# TIDA-00830_DRV888x.net
KiCad netlist of a schematic drawn in Altium Designer
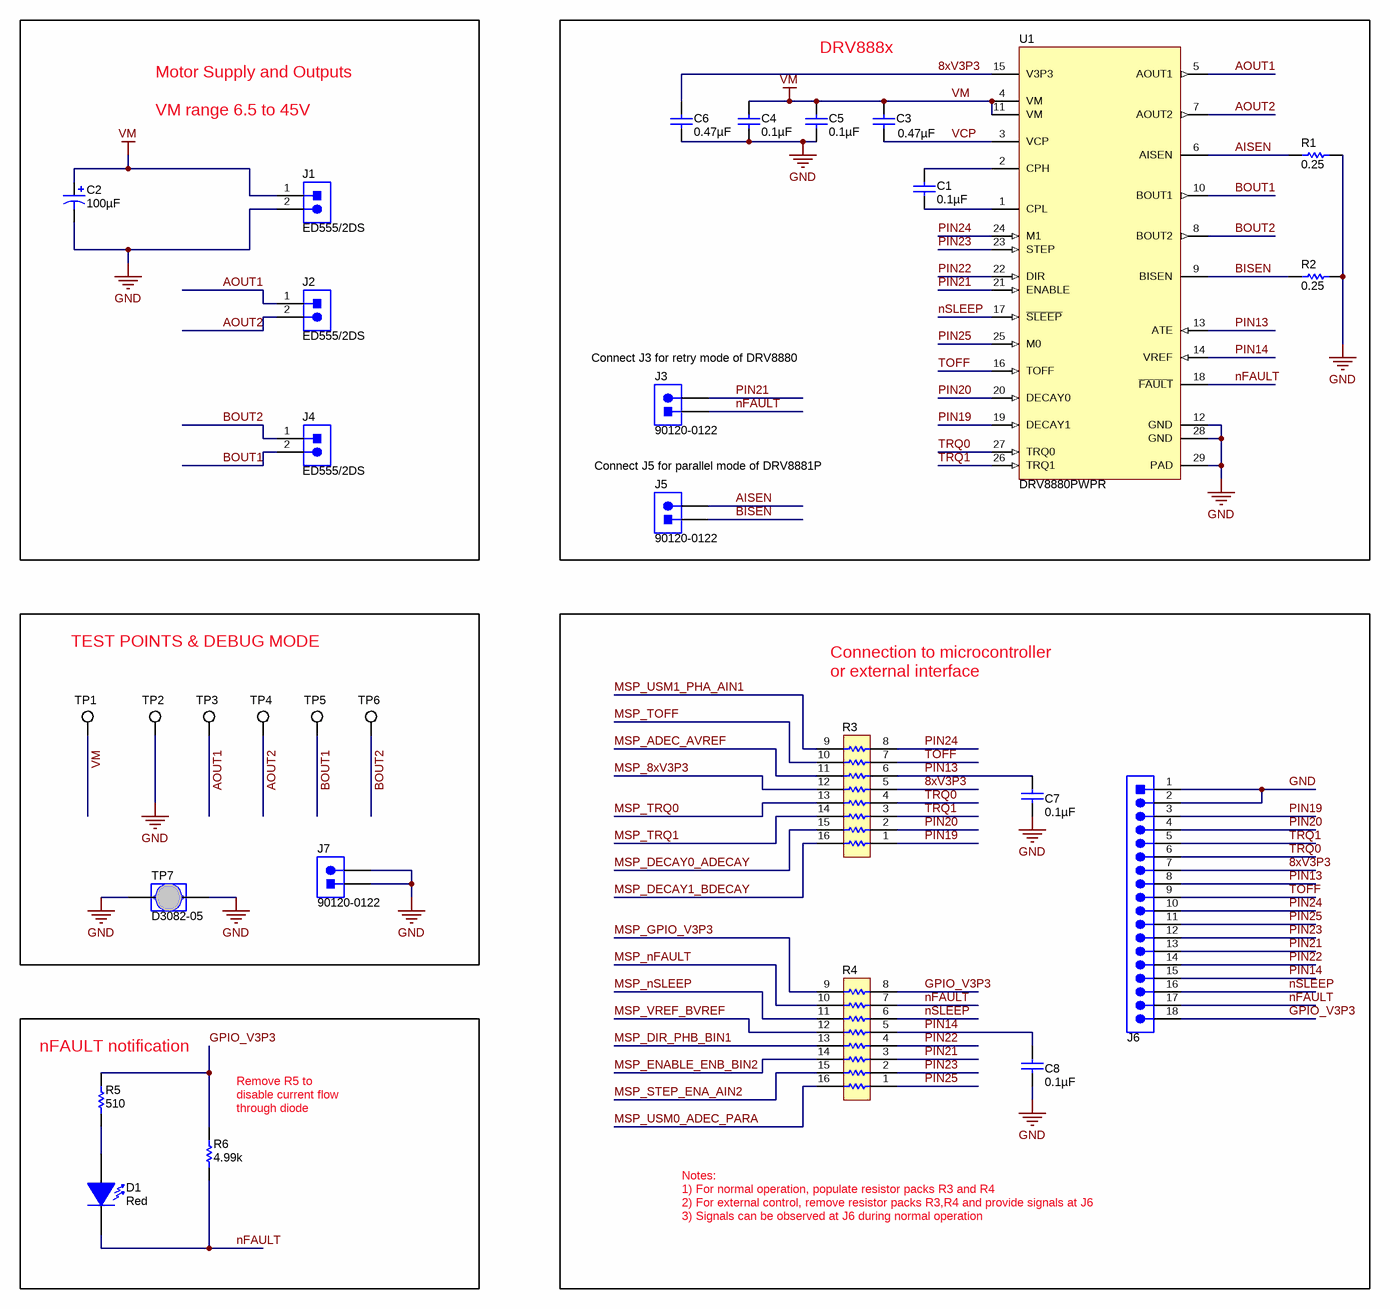
[diagram p0: TIDA-00830_DRV888x.SchDoc]

(export (version "E")
  (design (tool "Eeschema 10.0.6"))
  (components
    (comp (ref "C1")
      (value "C0805C104K1RACTU")
      (footprint "0805L")
      (description "CAP, CERM, 0.1 µF, 100 V, +/- 10%, X7R, 0805")
      (fields
        (field (name "VALUEDISPLAYED") "0.1µF")
        (field (name "MANUFACTURER") "Kemet")
        (field (name "PUBLISHER") "Texas Instruments")
      )
      (libsource (lib "Capacitor_Ceramic") (part "C0805C104K1RACTU"))
    )
    (comp (ref "C2")
      (value "EEE-FK1J101P")
      (footprint "SM_RADIAL_G")
      (description "CAP, AL, 100 µF, 63 V, +/- 20%, 0.35 ohm, SMD")
      (fields
        (field (name "MANUFACTURER") "Panasonic")
        (field (name "VALUEDISPLAYED") "100µF")
        (field (name "PUBLISHER") "Texas Instruments")
      )
      (libsource (lib "Capacitor_Aluminum") (part "EEE-FK1J101P"))
    )
    (comp (ref "C3")
      (value "C2012X7R1E474K")
      (footprint "0805L")
      (description "CAP, CERM, 0.47 µF, 25 V, +/- 10%, X7R, 0805")
      (fields
        (field (name "VALUEDISPLAYED") "0.47µF")
        (field (name "MANUFACTURER") "TDK")
        (field (name "PUBLISHER") "Texas Instruments")
      )
      (libsource (lib "Capacitor_Ceramic") (part "C2012X7R1E474K"))
    )
    (comp (ref "C4")
      (value "C0805C104K1RACTU")
      (footprint "0805L")
      (description "CAP, CERM, 0.1 µF, 100 V, +/- 10%, X7R, 0805")
      (fields
        (field (name "VALUEDISPLAYED") "0.1µF")
        (field (name "MANUFACTURER") "Kemet")
        (field (name "PUBLISHER") "Texas Instruments")
      )
      (libsource (lib "Capacitor_Ceramic") (part "C0805C104K1RACTU"))
    )
    (comp (ref "C5")
      (value "C0805C104K1RACTU")
      (footprint "0805L")
      (description "CAP, CERM, 0.1 µF, 100 V, +/- 10%, X7R, 0805")
      (fields
        (field (name "VALUEDISPLAYED") "0.1µF")
        (field (name "MANUFACTURER") "Kemet")
        (field (name "PUBLISHER") "Texas Instruments")
      )
      (libsource (lib "Capacitor_Ceramic") (part "C0805C104K1RACTU"))
    )
    (comp (ref "C6")
      (value "C0603C474K9RACTU")
      (footprint "0603L")
      (description "CAP, CERM, 0.47 µF, 6.3 V, +/- 10%, X7R, 0603")
      (fields
        (field (name "VALUEDISPLAYED") "0.47µF")
        (field (name "MANUFACTURER") "Kemet")
        (field (name "PUBLISHER") "Texas Instruments")
      )
      (libsource (lib "Capacitor_Ceramic") (part "C0603C474K9RACTU"))
    )
    (comp (ref "C7")
      (value "GRM155R61A104KA01D")
      (footprint "0402L")
      (description "CAP, CERM, 0.1 µF, 10 V, +/- 10%, X5R, 0402")
      (fields
        (field (name "MANUFACTURER") "MuRata")
        (field (name "VALUEDISPLAYED") "0.1µF")
        (field (name "PUBLISHER") "Texas Instruments")
      )
      (libsource (lib "Capacitor_Ceramic") (part "GRM155R61A104KA01D"))
    )
    (comp (ref "C8")
      (value "GRM155R61A104KA01D")
      (footprint "0402L")
      (description "CAP, CERM, 0.1 µF, 10 V, +/- 10%, X5R, 0402")
      (fields
        (field (name "MANUFACTURER") "MuRata")
        (field (name "VALUEDISPLAYED") "0.1µF")
        (field (name "PUBLISHER") "Texas Instruments")
      )
      (libsource (lib "Capacitor_Ceramic") (part "GRM155R61A104KA01D"))
    )
    (comp (ref "D1")
      (value "Red")
      (footprint "LED_LTST-C190_Red")
      (description "LED, Red, SMD")
      (fields
        (field (name "PARTNUMBER") "LTST-C190CKT")
        (field (name "MANUFACTURER") "Lite-On")
        (field (name "PUBLISHER") "Texas Instruments")
      )
      (libsource (lib "LED") (part "LTST-C190CKT"))
    )
    (comp (ref "J1")
      (value "ED555/2DS")
      (footprint "TERM_BLK_ED555-2DS")
      (description "Terminal Block, 6A, 3.5mm Pitch, 2-Pos, TH")
      (fields
        (field (name "MANUFACTURER") "On-Shore Technology")
        (field (name "SYMBOLCREATOR") "a0412235")
        (field (name "PUBLISHER") "Texas Instruments")
      )
      (libsource (lib "Connectors_Other") (part "ED555/2DS"))
    )
    (comp (ref "J2")
      (value "ED555/2DS")
      (footprint "TERM_BLK_ED555-2DS")
      (description "Terminal Block, 6A, 3.5mm Pitch, 2-Pos, TH")
      (fields
        (field (name "MANUFACTURER") "On-Shore Technology")
        (field (name "SYMBOLCREATOR") "a0412235")
        (field (name "PUBLISHER") "Texas Instruments")
      )
      (libsource (lib "Connectors_Other") (part "ED555/2DS"))
    )
    (comp (ref "J3")
      (value "90120-0122")
      (footprint "CONN_90120-0122")
      (description "Header, 100mil, 2x1, Tin, TH")
      (fields
        (field (name "MANUFACTURER") "Molex")
        (field (name "SYMBOLCREATOR") "a0412235")
        (field (name "PUBLISHER") "Texas Instruments")
      )
      (libsource (lib "Connectors_Molex") (part "90120-0122"))
    )
    (comp (ref "J4")
      (value "ED555/2DS")
      (footprint "TERM_BLK_ED555-2DS")
      (description "Terminal Block, 6A, 3.5mm Pitch, 2-Pos, TH")
      (fields
        (field (name "MANUFACTURER") "On-Shore Technology")
        (field (name "SYMBOLCREATOR") "a0412235")
        (field (name "PUBLISHER") "Texas Instruments")
      )
      (libsource (lib "Connectors_Other") (part "ED555/2DS"))
    )
    (comp (ref "J5")
      (value "90120-0122")
      (footprint "CONN_90120-0122")
      (description "Header, 100mil, 2x1, Tin, TH")
      (fields
        (field (name "MANUFACTURER") "Molex")
        (field (name "SYMBOLCREATOR") "a0412235")
        (field (name "PUBLISHER") "Texas Instruments")
      )
      (libsource (lib "Connectors_Molex") (part "90120-0122"))
    )
    (comp (ref "J6")
      (value "TSW-118-07-G-S")
      (footprint "TSW-118-07-G-S")
      (description "Header, 100mil, 18x1, Gold, TH")
      (fields
        (field (name "MANUFACTURER") "Samtec")
        (field (name "SYMBOLCREATOR") "a0411947")
        (field (name "PUBLISHER") "Texas Instruments")
      )
      (libsource (lib "Connectors_Samtec") (part "TSW-118-07-G-S"))
    )
    (comp (ref "J7")
      (value "90120-0122")
      (footprint "CONN_90120-0122")
      (description "Header, 100mil, 2x1, Tin, TH")
      (fields
        (field (name "MANUFACTURER") "Molex")
        (field (name "SYMBOLCREATOR") "a0412235")
        (field (name "PUBLISHER") "Texas Instruments")
      )
      (libsource (lib "Connectors_Molex") (part "90120-0122"))
    )
    (comp (ref "R1")
      (value "0.25")
      (footprint "2010L")
      (description "RES, 0.25, 1%, 1 W, 2010")
      (fields
        (field (name "PARTNUMBER") "CSRN2010FKR250")
        (field (name "MANUFACTURER") "Stackpole Electronics Inc")
        (field (name "PUBLISHER") "Texas Instruments")
      )
      (libsource (lib "Resistor_2010") (part "CSRN2010FKR250"))
    )
    (comp (ref "R2")
      (value "0.25")
      (footprint "2010L")
      (description "RES, 0.25, 1%, 1 W, 2010")
      (fields
        (field (name "PARTNUMBER") "CSRN2010FKR250")
        (field (name "MANUFACTURER") "Stackpole Electronics Inc")
        (field (name "PUBLISHER") "Texas Instruments")
      )
      (libsource (lib "Resistor_2010") (part "CSRN2010FKR250"))
    )
    (comp (ref "R3")
      (value "EXB-2HV330JV")
      (footprint "RESCAXS_EXB-2HV")
      (description "RES, 33, 5%, 0.0625 W, Resistor Array - 8x1")
      (fields
        (field (name "MANUFACTURER") "Panasonic")
        (field (name "SYMBOLCREATOR") "a0411947")
        (field (name "PUBLISHER") "Texas Instruments")
      )
      (libsource (lib "Resistor_OtherSMT") (part "EXB-2HV330JV"))
    )
    (comp (ref "R4")
      (value "EXB-2HV330JV")
      (footprint "RESCAXS_EXB-2HV")
      (description "RES, 33, 5%, 0.0625 W, Resistor Array - 8x1")
      (fields
        (field (name "MANUFACTURER") "Panasonic")
        (field (name "SYMBOLCREATOR") "a0411947")
        (field (name "PUBLISHER") "Texas Instruments")
      )
      (libsource (lib "Resistor_OtherSMT") (part "EXB-2HV330JV"))
    )
    (comp (ref "R5")
      (value "510")
      (footprint "0402L")
      (description "RES, 510, 5%, 0.063 W, 0402")
      (fields
        (field (name "PARTNUMBER") "CRCW0402510RJNED")
        (field (name "MANUFACTURER") "Vishay-Dale")
        (field (name "PUBLISHER") "Texas Instruments")
      )
      (libsource (lib "Resistor_0402") (part "CRCW0402510RJNED"))
    )
    (comp (ref "R6")
      (value "4.99k")
      (footprint "0402L")
      (description "RES, 4.99 k, 1%, 0.063 W, 0402")
      (fields
        (field (name "PARTNUMBER") "CRCW04024K99FKED")
        (field (name "MANUFACTURER") "Vishay-Dale")
        (field (name "PUBLISHER") "Texas Instruments")
      )
      (libsource (lib "Resistor_0402") (part "CRCW04024K99FKED"))
    )
    (comp (ref "TP1")
      (value "5016")
      (footprint "Testpoint_Keystone_Compact")
      (description "Test Point, Compact, SMT")
      (fields (field (name "MANUFACTURER") "Keystone") (field (name "PUBLISHER") "Texas Instruments"))
      (libsource (lib "Connectors_Keystone") (part "5016"))
    )
    (comp (ref "TP2")
      (value "5016")
      (footprint "Testpoint_Keystone_Compact")
      (description "Test Point, Compact, SMT")
      (fields (field (name "MANUFACTURER") "Keystone") (field (name "PUBLISHER") "Texas Instruments"))
      (libsource (lib "Connectors_Keystone") (part "5016"))
    )
    (comp (ref "TP3")
      (value "5016")
      (footprint "Testpoint_Keystone_Compact")
      (description "Test Point, Compact, SMT")
      (fields (field (name "MANUFACTURER") "Keystone") (field (name "PUBLISHER") "Texas Instruments"))
      (libsource (lib "Connectors_Keystone") (part "5016"))
    )
    (comp (ref "TP4")
      (value "5016")
      (footprint "Testpoint_Keystone_Compact")
      (description "Test Point, Compact, SMT")
      (fields (field (name "MANUFACTURER") "Keystone") (field (name "PUBLISHER") "Texas Instruments"))
      (libsource (lib "Connectors_Keystone") (part "5016"))
    )
    (comp (ref "TP5")
      (value "5016")
      (footprint "Testpoint_Keystone_Compact")
      (description "Test Point, Compact, SMT")
      (fields (field (name "MANUFACTURER") "Keystone") (field (name "PUBLISHER") "Texas Instruments"))
      (libsource (lib "Connectors_Keystone") (part "5016"))
    )
    (comp (ref "TP6")
      (value "5016")
      (footprint "Testpoint_Keystone_Compact")
      (description "Test Point, Compact, SMT")
      (fields (field (name "MANUFACTURER") "Keystone") (field (name "PUBLISHER") "Texas Instruments"))
      (libsource (lib "Connectors_Keystone") (part "5016"))
    )
    (comp (ref "TP7")
      (value "D3082-05")
      (footprint "Harwin_D3082-05")
      (description "1mm Uninsulated Shorting Plug, 10.16mm spacing, TH")
      (fields
        (field (name "MANUFACTURER") "Harwin")
        (field (name "SYMBOLCREATOR") "a0799628")
        (field (name "PUBLISHER") "Texas Instruments")
      )
      (libsource (lib "Connectors_Other") (part "D3082-05"))
    )
    (comp (ref "U1")
      (value "DRV8880PWPR")
      (footprint "PWP0028C_N")
      (description "2-A 45-V 1/16-μstep Stepper Motor Driver With AutoTune, PWP0028C")
      (fields
        (field (name "ALTERNATE PARTNUMBER") "DRV8880PWP")
        (field (name "MANUFACTURER") "Texas Instruments")
        (field (name "SYMBOLCREATOR") "Altium")
        (field (name "PUBLISHER") "Texas Instruments")
      )
      (libsource (lib "TI_Pre_RTM") (part "DRV8880PWPR"))
    )
  )
  (nets
    (net (code "1") (name "/8xV3P3") (class "Default")
      (node (ref "C6") (pin "1") (pinfunction "1_1") (pintype "passive"))
      (node (ref "J6") (pin "7") (pinfunction "7_7") (pintype "passive"))
      (node (ref "R3") (pin "5") (pinfunction "5_5") (pintype "passive"))
      (node (ref "U1") (pin "15") (pinfunction "V3P3_15") (pintype "power_in"))
    )
    (net (code "2") (name "/AISEN") (class "Default")
      (node (ref "J5") (pin "2") (pinfunction "2_2") (pintype "passive"))
      (node (ref "R1") (pin "2") (pinfunction "2_2") (pintype "passive"))
      (node (ref "U1") (pin "6") (pinfunction "AISEN_6") (pintype "passive"))
    )
    (net (code "3") (name "/AOUT1") (class "Default")
      (node (ref "J2") (pin "1") (pinfunction "1_1") (pintype "passive"))
      (node (ref "TP3") (pin "1") (pintype "passive"))
      (node (ref "U1") (pin "5") (pinfunction "AOUT1_5") (pintype "output"))
    )
    (net (code "4") (name "/AOUT2") (class "Default")
      (node (ref "J2") (pin "2") (pinfunction "2_2") (pintype "passive"))
      (node (ref "TP4") (pin "1") (pintype "passive"))
      (node (ref "U1") (pin "7") (pinfunction "AOUT2_7") (pintype "output"))
    )
    (net (code "5") (name "/BISEN") (class "Default")
      (node (ref "J5") (pin "1") (pinfunction "1_1") (pintype "passive"))
      (node (ref "R2") (pin "2") (pinfunction "2_2") (pintype "passive"))
      (node (ref "U1") (pin "9") (pinfunction "BISEN_9") (pintype "passive"))
    )
    (net (code "6") (name "/BOUT1") (class "Default")
      (node (ref "J4") (pin "2") (pinfunction "2_2") (pintype "passive"))
      (node (ref "TP5") (pin "1") (pintype "passive"))
      (node (ref "U1") (pin "10") (pinfunction "BOUT1_10") (pintype "output"))
    )
    (net (code "7") (name "/BOUT2") (class "Default")
      (node (ref "J4") (pin "1") (pinfunction "1_1") (pintype "passive"))
      (node (ref "TP6") (pin "1") (pintype "passive"))
      (node (ref "U1") (pin "8") (pinfunction "BOUT2_8") (pintype "output"))
    )
    (net (code "8") (name "/GPIO_V3P3") (class "Default")
      (node (ref "J6") (pin "18") (pinfunction "18_18") (pintype "passive"))
      (node (ref "R4") (pin "8") (pinfunction "8_8") (pintype "passive"))
      (node (ref "R5") (pin "2") (pinfunction "2_2") (pintype "passive"))
      (node (ref "R6") (pin "2") (pinfunction "2_2") (pintype "passive"))
    )
    (net (code "9") (name "/MSP_8xV3P3") (class "Default")
      (node (ref "R3") (pin "12") (pinfunction "12_12") (pintype "passive"))
    )
    (net (code "10") (name "/MSP_ADEC_AVREF") (class "Default")
      (node (ref "R3") (pin "11") (pinfunction "11_11") (pintype "passive"))
    )
    (net (code "11") (name "/MSP_DECAY0_ADECAY") (class "Default")
      (node (ref "R3") (pin "15") (pinfunction "15_15") (pintype "passive"))
    )
    (net (code "12") (name "/MSP_DECAY1_BDECAY") (class "Default")
      (node (ref "R3") (pin "16") (pinfunction "16_16") (pintype "passive"))
    )
    (net (code "13") (name "/MSP_DIR_PHB_BIN1") (class "Default")
      (node (ref "R4") (pin "13") (pinfunction "13_13") (pintype "passive"))
    )
    (net (code "14") (name "/MSP_ENABLE_ENB_BIN2") (class "Default")
      (node (ref "R4") (pin "14") (pinfunction "14_14") (pintype "passive"))
    )
    (net (code "15") (name "/MSP_GPIO_V3P3") (class "Default")
      (node (ref "R4") (pin "9") (pinfunction "9_9") (pintype "passive"))
    )
    (net (code "16") (name "/MSP_STEP_ENA_AIN2") (class "Default")
      (node (ref "R4") (pin "15") (pinfunction "15_15") (pintype "passive"))
    )
    (net (code "17") (name "/MSP_TOFF") (class "Default")
      (node (ref "R3") (pin "10") (pinfunction "10_10") (pintype "passive"))
    )
    (net (code "18") (name "/MSP_TRQ0") (class "Default")
      (node (ref "R3") (pin "13") (pinfunction "13_13") (pintype "passive"))
    )
    (net (code "19") (name "/MSP_TRQ1") (class "Default")
      (node (ref "R3") (pin "14") (pinfunction "14_14") (pintype "passive"))
    )
    (net (code "20") (name "/MSP_USM0_ADEC_PARA") (class "Default")
      (node (ref "R4") (pin "16") (pinfunction "16_16") (pintype "passive"))
    )
    (net (code "21") (name "/MSP_USM1_PHA_AIN1") (class "Default")
      (node (ref "R3") (pin "9") (pinfunction "9_9") (pintype "passive"))
    )
    (net (code "22") (name "/MSP_VREF_BVREF") (class "Default")
      (node (ref "R4") (pin "12") (pinfunction "12_12") (pintype "passive"))
    )
    (net (code "23") (name "/MSP_nFAULT") (class "Default")
      (node (ref "R4") (pin "10") (pinfunction "10_10") (pintype "passive"))
    )
    (net (code "24") (name "/MSP_nSLEEP") (class "Default")
      (node (ref "R4") (pin "11") (pinfunction "11_11") (pintype "passive"))
    )
    (net (code "25") (name "/PIN13") (class "Default")
      (node (ref "C7") (pin "1") (pinfunction "1_1") (pintype "passive"))
      (node (ref "J6") (pin "8") (pinfunction "8_8") (pintype "passive"))
      (node (ref "R3") (pin "6") (pinfunction "6_6") (pintype "passive"))
      (node (ref "U1") (pin "13") (pinfunction "ATE_13") (pintype "input"))
    )
    (net (code "26") (name "/PIN14") (class "Default")
      (node (ref "C8") (pin "1") (pinfunction "1_1") (pintype "passive"))
      (node (ref "J6") (pin "15") (pinfunction "15_15") (pintype "passive"))
      (node (ref "R4") (pin "5") (pinfunction "5_5") (pintype "passive"))
      (node (ref "U1") (pin "14") (pinfunction "VREF_14") (pintype "input"))
    )
    (net (code "27") (name "/PIN19") (class "Default")
      (node (ref "J6") (pin "3") (pinfunction "3_3") (pintype "passive"))
      (node (ref "R3") (pin "1") (pinfunction "1_1") (pintype "passive"))
      (node (ref "U1") (pin "19") (pinfunction "DECAY1_19") (pintype "input"))
    )
    (net (code "28") (name "/PIN20") (class "Default")
      (node (ref "J6") (pin "4") (pinfunction "4_4") (pintype "passive"))
      (node (ref "R3") (pin "2") (pinfunction "2_2") (pintype "passive"))
      (node (ref "U1") (pin "20") (pinfunction "DECAY0_20") (pintype "input"))
    )
    (net (code "29") (name "/PIN21") (class "Default")
      (node (ref "J3") (pin "2") (pinfunction "2_2") (pintype "passive"))
      (node (ref "J6") (pin "13") (pinfunction "13_13") (pintype "passive"))
      (node (ref "R4") (pin "3") (pinfunction "3_3") (pintype "passive"))
      (node (ref "U1") (pin "21") (pinfunction "ENABLE_21") (pintype "input"))
    )
    (net (code "30") (name "/PIN22") (class "Default")
      (node (ref "J6") (pin "14") (pinfunction "14_14") (pintype "passive"))
      (node (ref "R4") (pin "4") (pinfunction "4_4") (pintype "passive"))
      (node (ref "U1") (pin "22") (pinfunction "DIR_22") (pintype "input"))
    )
    (net (code "31") (name "/PIN23") (class "Default")
      (node (ref "J6") (pin "12") (pinfunction "12_12") (pintype "passive"))
      (node (ref "R4") (pin "2") (pinfunction "2_2") (pintype "passive"))
      (node (ref "U1") (pin "23") (pinfunction "STEP_23") (pintype "input"))
    )
    (net (code "32") (name "/PIN24") (class "Default")
      (node (ref "J6") (pin "10") (pinfunction "10_10") (pintype "passive"))
      (node (ref "R3") (pin "8") (pinfunction "8_8") (pintype "passive"))
      (node (ref "U1") (pin "24") (pinfunction "M1_24") (pintype "input"))
    )
    (net (code "33") (name "/PIN25") (class "Default")
      (node (ref "J6") (pin "11") (pinfunction "11_11") (pintype "passive"))
      (node (ref "R4") (pin "1") (pinfunction "1_1") (pintype "passive"))
      (node (ref "U1") (pin "25") (pinfunction "M0_25") (pintype "input"))
    )
    (net (code "34") (name "/TOFF") (class "Default")
      (node (ref "J6") (pin "9") (pinfunction "9_9") (pintype "passive"))
      (node (ref "R3") (pin "7") (pinfunction "7_7") (pintype "passive"))
      (node (ref "U1") (pin "16") (pinfunction "TOFF_16") (pintype "input"))
    )
    (net (code "35") (name "/TRQ0") (class "Default")
      (node (ref "J6") (pin "6") (pinfunction "6_6") (pintype "passive"))
      (node (ref "R3") (pin "4") (pinfunction "4_4") (pintype "passive"))
      (node (ref "U1") (pin "27") (pinfunction "TRQ0_27") (pintype "input"))
    )
    (net (code "36") (name "/TRQ1") (class "Default")
      (node (ref "J6") (pin "5") (pinfunction "5_5") (pintype "passive"))
      (node (ref "R3") (pin "3") (pinfunction "3_3") (pintype "passive"))
      (node (ref "U1") (pin "26") (pinfunction "TRQ1_26") (pintype "input"))
    )
    (net (code "37") (name "/VCP") (class "Default")
      (node (ref "C3") (pin "1") (pinfunction "1_1") (pintype "passive"))
      (node (ref "U1") (pin "3") (pinfunction "VCP_3") (pintype "passive"))
    )
    (net (code "38") (name "/nFAULT") (class "Default")
      (node (ref "D1") (pin "2") (pinfunction "K_2") (pintype "passive"))
      (node (ref "J3") (pin "1") (pinfunction "1_1") (pintype "passive"))
      (node (ref "J6") (pin "17") (pinfunction "17_17") (pintype "passive"))
      (node (ref "R4") (pin "7") (pinfunction "7_7") (pintype "passive"))
      (node (ref "R6") (pin "1") (pinfunction "1_1") (pintype "passive"))
      (node (ref "U1") (pin "18") (pinfunction "FAULT_18") (pintype "open_collector"))
    )
    (net (code "39") (name "/nSLEEP") (class "Default")
      (node (ref "J6") (pin "16") (pinfunction "16_16") (pintype "passive"))
      (node (ref "R4") (pin "6") (pinfunction "6_6") (pintype "passive"))
      (node (ref "U1") (pin "17") (pinfunction "SLEEP_17") (pintype "input"))
    )
    (net (code "40") (name "GND") (class "Default")
      (node (ref "C2") (pin "2") (pinfunction "-_2") (pintype "passive"))
      (node (ref "C4") (pin "1") (pinfunction "1_1") (pintype "passive"))
      (node (ref "C5") (pin "1") (pinfunction "1_1") (pintype "passive"))
      (node (ref "C6") (pin "2") (pinfunction "2_2") (pintype "passive"))
      (node (ref "C7") (pin "2") (pinfunction "2_2") (pintype "passive"))
      (node (ref "C8") (pin "2") (pinfunction "2_2") (pintype "passive"))
      (node (ref "J1") (pin "2") (pinfunction "2_2") (pintype "passive"))
      (node (ref "J6") (pin "1") (pinfunction "1_1") (pintype "passive"))
      (node (ref "J6") (pin "2") (pinfunction "2_2") (pintype "passive"))
      (node (ref "J7") (pin "1") (pinfunction "1_1") (pintype "passive"))
      (node (ref "J7") (pin "2") (pinfunction "2_2") (pintype "passive"))
      (node (ref "R1") (pin "1") (pinfunction "1_1") (pintype "passive"))
      (node (ref "R2") (pin "1") (pinfunction "1_1") (pintype "passive"))
      (node (ref "TP2") (pin "1") (pintype "passive"))
      (node (ref "TP7") (pin "1") (pinfunction "1_1") (pintype "passive"))
      (node (ref "TP7") (pin "2") (pinfunction "2_2") (pintype "passive"))
      (node (ref "U1") (pin "12") (pinfunction "GND_12") (pintype "power_in"))
      (node (ref "U1") (pin "28") (pinfunction "GND_28") (pintype "power_in"))
      (node (ref "U1") (pin "29") (pinfunction "PAD_29") (pintype "power_in"))
    )
    (net (code "41") (name "Net-(D1-A)") (class "Default")
      (node (ref "D1") (pin "1") (pinfunction "A_1") (pintype "passive"))
      (node (ref "R5") (pin "1") (pinfunction "1_1") (pintype "passive"))
    )
    (net (code "42") (name "Net-(U1-CPH)") (class "Default")
      (node (ref "C1") (pin "2") (pinfunction "2_2") (pintype "passive"))
      (node (ref "U1") (pin "2") (pinfunction "CPH_2") (pintype "passive"))
    )
    (net (code "43") (name "Net-(U1-CPL)") (class "Default")
      (node (ref "C1") (pin "1") (pinfunction "1_1") (pintype "passive"))
      (node (ref "U1") (pin "1") (pinfunction "CPL_1") (pintype "passive"))
    )
    (net (code "44") (name "VM") (class "Default")
      (node (ref "C2") (pin "1") (pinfunction "+_1") (pintype "passive"))
      (node (ref "C3") (pin "2") (pinfunction "2_2") (pintype "passive"))
      (node (ref "C4") (pin "2") (pinfunction "2_2") (pintype "passive"))
      (node (ref "C5") (pin "2") (pinfunction "2_2") (pintype "passive"))
      (node (ref "J1") (pin "1") (pinfunction "1_1") (pintype "passive"))
      (node (ref "TP1") (pin "1") (pintype "passive"))
      (node (ref "U1") (pin "11") (pinfunction "VM_11") (pintype "power_in"))
      (node (ref "U1") (pin "4") (pinfunction "VM_4") (pintype "power_in"))
    )
  )
)
